# RTU_LMG_LoRa_Module.net
KiCad netlist of a schematic drawn in Altium Designer
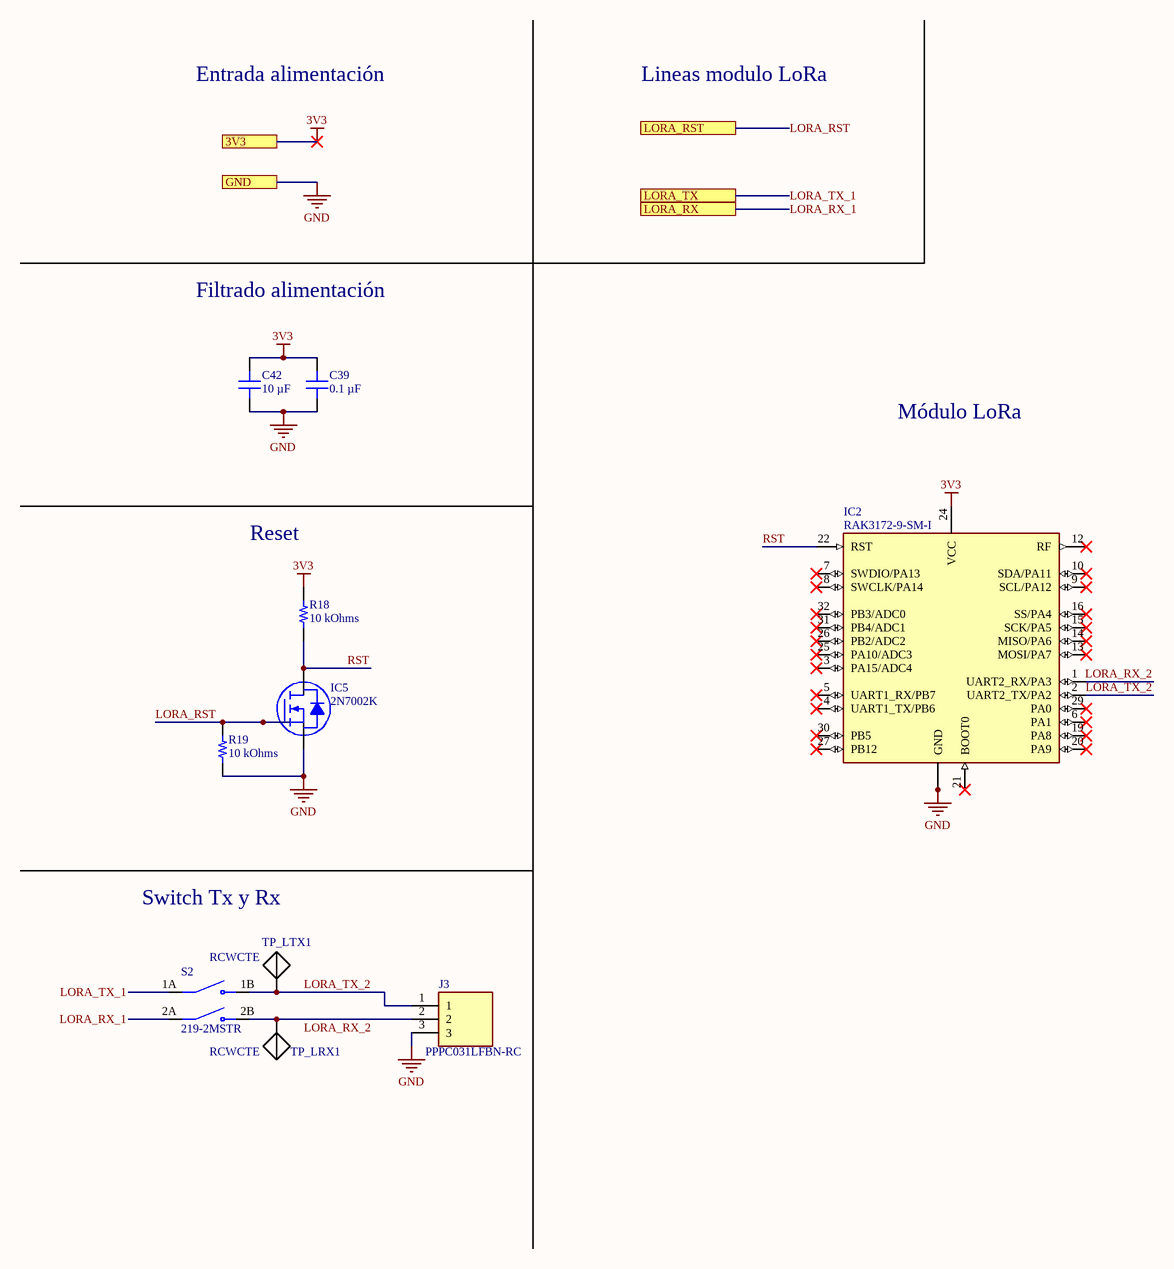
[diagram p0: RTU_LMG_LoRa_Module.SchDoc]

(export (version "E")
  (design (tool "Eeschema 10.0.6"))
  (components
    (comp (ref "C39")
      (value "0.1 µF")
      (footprint "MURATA GRM155 0402_1005")
      (description "CAP CER 0.1UF 50V X7R 0402")
      (fields
        (field (name "PART NUMBER") "GRM155R71H104KE14D")
        (field (name "MANUFACTURER") "Murata Electronics")
      )
      (libsource (lib "Celestial Altium Library - altium_library") (part "Capacitor"))
    )
    (comp (ref "C42")
      (value "10 µF")
      (footprint "CAP 0805_2012")
      (description "CAP CER 10UF 16V X5R 0805")
      (fields
        (field (name "PART NUMBER") "CL21A106KOQNNNE")
        (field (name "MANUFACTURER") "Samsung Electro-Mechanics")
      )
      (libsource (lib "Celestial Altium Library - altium_library") (part "Capacitor"))
    )
    (comp (ref "IC2")
      (value "RAK3172-9-SM-I")
      (footprint "RAK3172-9-SM-I")
      (description "LoRaWAN module from RAK")
      (fields (field (name "MF") "Shenzhen RAKwireless Technology Co.,Ltd."))
      (libsource (lib "DIN_DC_Base_Board_components") (part "RAK3172-9-SM-I"))
    )
    (comp (ref "IC5")
      (value "2N7002K")
      (footprint "ON SEMI SOT-23-3")
      (description "MOSFET N-CH 60V 300MA SOT23")
      (fields (field (name "MANUFACTURER") "ON Semiconductor"))
      (libsource (lib "Celestial Altium Library - altium_library") (part "ON SEMI MOSFET N-CH SOT-23-3"))
    )
    (comp (ref "J3")
      (value "PPPC031LFBN-RC")
      (footprint "PPPC031LFBN-RC")
      (description "Connector")
      (libsource (lib "DIN_DC_Base_Board_components") (part "PPPC031LFBN-RC"))
    )
    (comp (ref "R18")
      (value "10 kOhms")
      (footprint "YAGEO RES 0603_1608")
      (description "RES 10K OHM 1% 1/10W 0603")
      (fields (field (name "PART NUMBER") "RC0603FR-0710KL") (field (name "MANUFACTURER") "Yageo"))
      (libsource (lib "Celestial Altium Library - altium_library") (part "Resistor"))
    )
    (comp (ref "R19")
      (value "10 kOhms")
      (footprint "YAGEO RES 0603_1608")
      (description "RES 10K OHM 1% 1/10W 0603")
      (fields (field (name "PART NUMBER") "RC0603FR-0710KL") (field (name "MANUFACTURER") "Yageo"))
      (libsource (lib "Celestial Altium Library - altium_library") (part "Resistor"))
    )
    (comp (ref "S2")
      (value "219-2MSTR")
      (footprint "SW_219-2MSTR")
      (description "Dip Switch SPST 2 Position Surface Mount Slide (Standard) Actuator 100mA 20VDC")
      (fields (field (name "MF") "CTS Electrocomponents"))
      (libsource (lib "DIN_DC_Base_Board_components") (part "219-2MSTR"))
    )
    (comp (ref "TP_LRX1")
      (value "RCWCTE")
      (footprint "RCWCTE")
      (description "- PC Test Point - - Plating Surface Mount Mounting Type")
      (fields (field (name "MF") "KOA Speer") (field (name "DIGI-KEY_PART_NUMBER") "2019-RCWCTETR-ND"))
      (libsource (lib "DIN_DC_Base_Board_components") (part "RCWCTE"))
    )
    (comp (ref "TP_LTX1")
      (value "RCWCTE")
      (footprint "RCWCTE")
      (description "- PC Test Point - - Plating Surface Mount Mounting Type")
      (fields (field (name "MF") "KOA Speer") (field (name "DIGI-KEY_PART_NUMBER") "2019-RCWCTETR-ND"))
      (libsource (lib "DIN_DC_Base_Board_components") (part "RCWCTE"))
    )
  )
  (nets
    (net (code "1") (name "/LORA_RST") (class "Default")
      (node (ref "IC5") (pin "1") (pinfunction "G_1") (pintype "passive"))
      (node (ref "R19") (pin "1") (pinfunction "1_1") (pintype "passive"))
    )
    (net (code "2") (name "/LORA_RX_1") (class "Default")
      (node (ref "S2") (pin "2A") (pinfunction "COM2_2A") (pintype "passive"))
    )
    (net (code "3") (name "/LORA_RX_2") (class "Default")
      (node (ref "IC2") (pin "1") (pinfunction "UART2_RX/PA3_1") (pintype "bidirectional"))
      (node (ref "J3") (pin "2") (pinfunction "2_2") (pintype "passive"))
      (node (ref "S2") (pin "2B") (pinfunction "NO2_2B") (pintype "passive"))
      (node (ref "TP_LRX1") (pin "1") (pinfunction "TP_1") (pintype "passive"))
    )
    (net (code "4") (name "/LORA_TX_1") (class "Default")
      (node (ref "S2") (pin "1A") (pinfunction "COM1_1A") (pintype "passive"))
    )
    (net (code "5") (name "/LORA_TX_2") (class "Default")
      (node (ref "IC2") (pin "2") (pinfunction "UART2_TX/PA2_2") (pintype "bidirectional"))
      (node (ref "J3") (pin "1") (pinfunction "1_1") (pintype "passive"))
      (node (ref "S2") (pin "1B") (pinfunction "NO1_1B") (pintype "passive"))
      (node (ref "TP_LTX1") (pin "1") (pinfunction "TP_1") (pintype "passive"))
    )
    (net (code "6") (name "/RST") (class "Default")
      (node (ref "IC2") (pin "22") (pinfunction "RST_22") (pintype "input"))
      (node (ref "IC5") (pin "3") (pinfunction "D_3") (pintype "passive"))
      (node (ref "R18") (pin "2") (pinfunction "2_2") (pintype "passive"))
    )
    (net (code "7") (name "3V3") (class "Default")
      (node (ref "C39") (pin "1") (pinfunction "1_1") (pintype "passive"))
      (node (ref "C42") (pin "2") (pinfunction "2_2") (pintype "passive"))
      (node (ref "IC2") (pin "24") (pinfunction "VCC_24") (pintype "power_in"))
      (node (ref "R18") (pin "1") (pinfunction "1_1") (pintype "passive"))
    )
    (net (code "8") (name "GND") (class "Default")
      (node (ref "C39") (pin "2") (pinfunction "2_2") (pintype "passive"))
      (node (ref "C42") (pin "1") (pinfunction "1_1") (pintype "passive"))
      (node (ref "IC2") (pin "11") (pinfunction "GND_11") (pintype "power_in"))
      (node (ref "IC2") (pin "17") (pinfunction "GND_17") (pintype "power_in"))
      (node (ref "IC2") (pin "18") (pinfunction "GND_18") (pintype "power_in"))
      (node (ref "IC2") (pin "23") (pinfunction "GND_23") (pintype "power_in"))
      (node (ref "IC2") (pin "28") (pinfunction "GND_28") (pintype "power_in"))
      (node (ref "IC5") (pin "2") (pinfunction "S_2") (pintype "passive"))
      (node (ref "J3") (pin "3") (pinfunction "3_3") (pintype "passive"))
      (node (ref "R19") (pin "2") (pinfunction "2_2") (pintype "passive"))
    )
    (net (code "9") (name "unconnected-(IC2-BOOT0-Pad21)") (class "Default")
      (node (ref "IC2") (pin "21") (pinfunction "BOOT0_21") (pintype "input+no_connect"))
    )
    (net (code "10") (name "unconnected-(IC2-MISO{slash}PA6-Pad14)") (class "Default")
      (node (ref "IC2") (pin "14") (pinfunction "MISO/PA6_14") (pintype "bidirectional+no_connect"))
    )
    (net (code "11") (name "unconnected-(IC2-MOSI{slash}PA7-Pad13)") (class "Default")
      (node (ref "IC2") (pin "13") (pinfunction "MOSI/PA7_13") (pintype "bidirectional+no_connect"))
    )
    (net (code "12") (name "unconnected-(IC2-PA0-Pad29)") (class "Default")
      (node (ref "IC2") (pin "29") (pinfunction "PA0_29") (pintype "bidirectional+no_connect"))
    )
    (net (code "13") (name "unconnected-(IC2-PA1-Pad6)") (class "Default")
      (node (ref "IC2") (pin "6") (pinfunction "PA1_6") (pintype "bidirectional+no_connect"))
    )
    (net (code "14") (name "unconnected-(IC2-PA8-Pad19)") (class "Default")
      (node (ref "IC2") (pin "19") (pinfunction "PA8_19") (pintype "bidirectional+no_connect"))
    )
    (net (code "15") (name "unconnected-(IC2-PA9-Pad20)") (class "Default")
      (node (ref "IC2") (pin "20") (pinfunction "PA9_20") (pintype "bidirectional+no_connect"))
    )
    (net (code "16") (name "unconnected-(IC2-PA10{slash}ADC3-Pad25)") (class "Default")
      (node (ref "IC2") (pin "25") (pinfunction "PA10/ADC3_25") (pintype "bidirectional+no_connect"))
    )
    (net (code "17") (name "unconnected-(IC2-PA15{slash}ADC4-Pad3)") (class "Default")
      (node (ref "IC2") (pin "3") (pinfunction "PA15/ADC4_3") (pintype "bidirectional+no_connect"))
    )
    (net (code "18") (name "unconnected-(IC2-PB2{slash}ADC2-Pad26)") (class "Default")
      (node (ref "IC2") (pin "26") (pinfunction "PB2/ADC2_26") (pintype "bidirectional+no_connect"))
    )
    (net (code "19") (name "unconnected-(IC2-PB3{slash}ADC0-Pad32)") (class "Default")
      (node (ref "IC2") (pin "32") (pinfunction "PB3/ADC0_32") (pintype "bidirectional+no_connect"))
    )
    (net (code "20") (name "unconnected-(IC2-PB4{slash}ADC1-Pad31)") (class "Default")
      (node (ref "IC2") (pin "31") (pinfunction "PB4/ADC1_31") (pintype "bidirectional+no_connect"))
    )
    (net (code "21") (name "unconnected-(IC2-PB5-Pad30)") (class "Default")
      (node (ref "IC2") (pin "30") (pinfunction "PB5_30") (pintype "bidirectional+no_connect"))
    )
    (net (code "22") (name "unconnected-(IC2-PB12-Pad27)") (class "Default")
      (node (ref "IC2") (pin "27") (pinfunction "PB12_27") (pintype "bidirectional+no_connect"))
    )
    (net (code "23") (name "unconnected-(IC2-RF-Pad12)") (class "Default")
      (node (ref "IC2") (pin "12") (pinfunction "RF_12") (pintype "output+no_connect"))
    )
    (net (code "24") (name "unconnected-(IC2-SCK{slash}PA5-Pad15)") (class "Default")
      (node (ref "IC2") (pin "15") (pinfunction "SCK/PA5_15") (pintype "bidirectional+no_connect"))
    )
    (net (code "25") (name "unconnected-(IC2-SCL{slash}PA12-Pad9)") (class "Default")
      (node (ref "IC2") (pin "9") (pinfunction "SCL/PA12_9") (pintype "bidirectional+no_connect"))
    )
    (net (code "26") (name "unconnected-(IC2-SDA{slash}PA11-Pad10)") (class "Default")
      (node (ref "IC2") (pin "10") (pinfunction "SDA/PA11_10") (pintype "bidirectional+no_connect"))
    )
    (net (code "27") (name "unconnected-(IC2-SS{slash}PA4-Pad16)") (class "Default")
      (node (ref "IC2") (pin "16") (pinfunction "SS/PA4_16") (pintype "bidirectional+no_connect"))
    )
    (net (code "28") (name "unconnected-(IC2-SWCLK{slash}PA14-Pad8)") (class "Default")
      (node (ref "IC2") (pin "8") (pinfunction "SWCLK/PA14_8") (pintype "bidirectional+no_connect"))
    )
    (net (code "29") (name "unconnected-(IC2-SWDIO{slash}PA13-Pad7)") (class "Default")
      (node (ref "IC2") (pin "7") (pinfunction "SWDIO/PA13_7") (pintype "bidirectional+no_connect"))
    )
    (net (code "30") (name "unconnected-(IC2-UART1_RX{slash}PB7-Pad5)") (class "Default")
      (node (ref "IC2") (pin "5") (pinfunction "UART1_RX/PB7_5") (pintype "bidirectional+no_connect"))
    )
    (net (code "31") (name "unconnected-(IC2-UART1_TX{slash}PB6-Pad4)") (class "Default")
      (node (ref "IC2") (pin "4") (pinfunction "UART1_TX/PB6_4") (pintype "bidirectional+no_connect"))
    )
  )
)
